# PCB-CMB-5-SHLD-3x5-1208.net
KiCad netlist of a schematic drawn in EAGLE
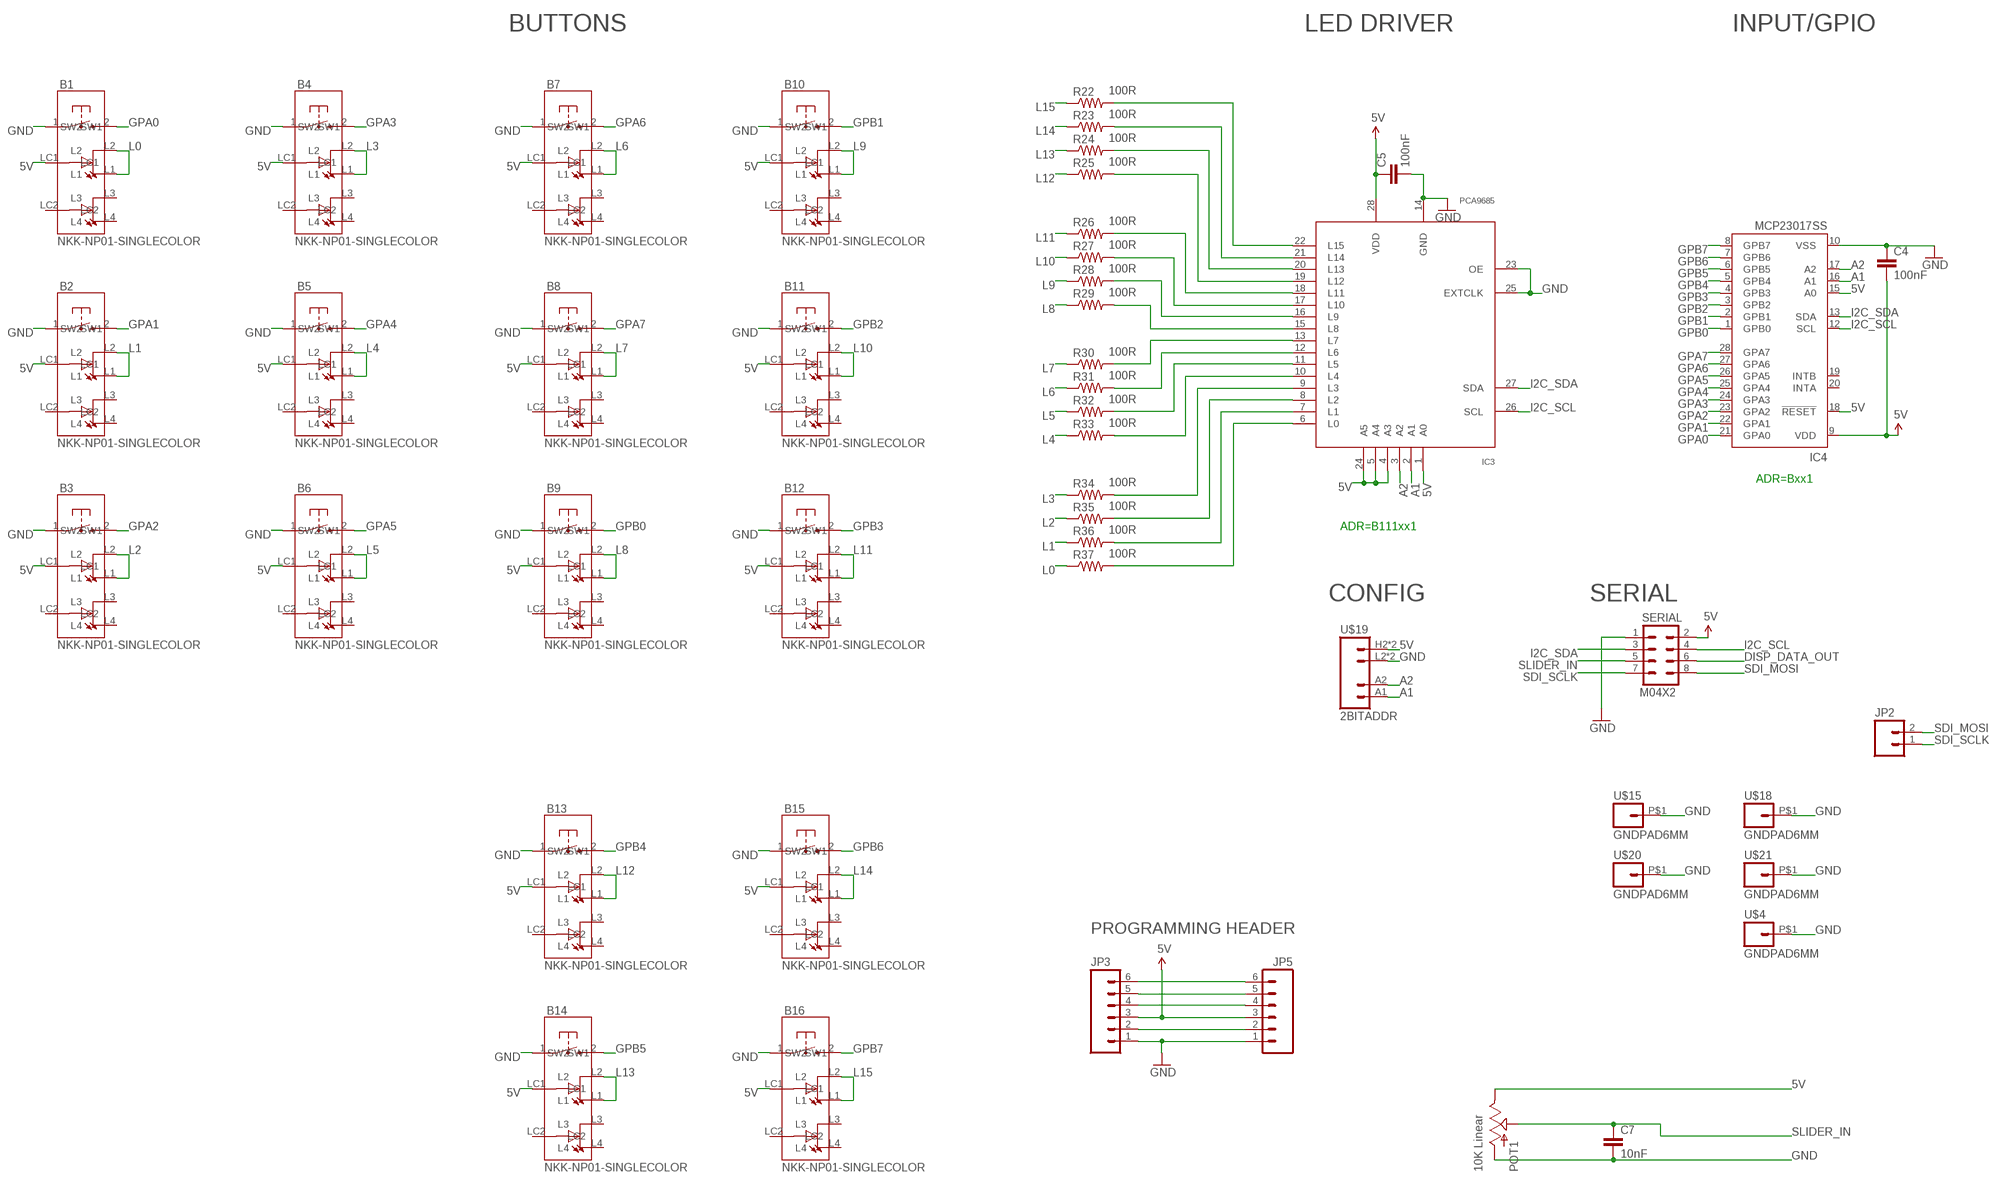
[diagram p0: schematic, sheet 1, part 1 of 2]
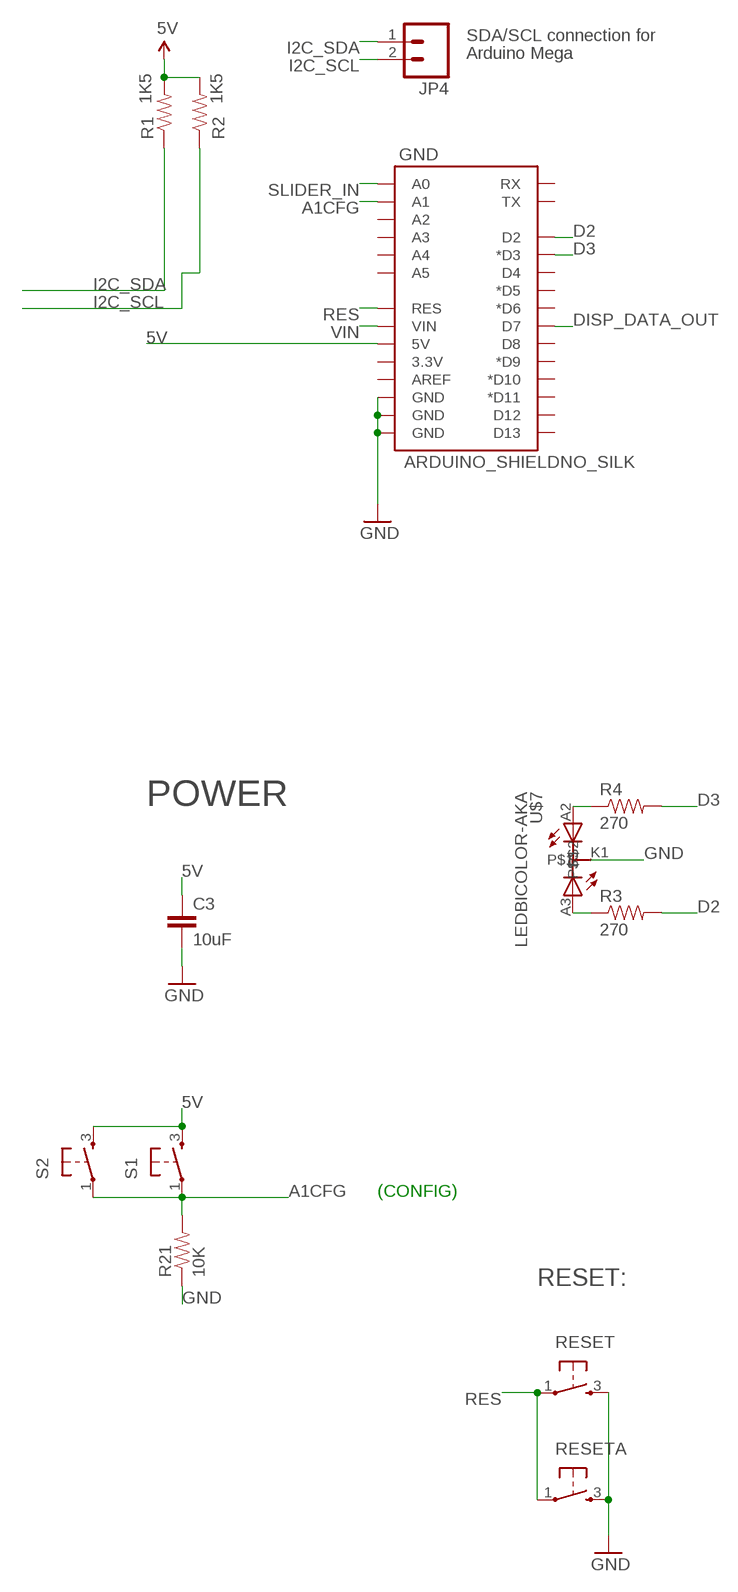
[diagram p1: schematic, sheet 1, part 2 of 2]

(export (version "E")
  (design (tool "Eeschema 10.0.6"))
  (components
    (comp (ref "B1")
      (value "NKK-NP01-SINGLECOLOR")
      (footprint "eagle-import:NKK-NP01")
      (libsource (lib "eagle-import") (part "NKK-NP01-SINGLECOLOR"))
    )
    (comp (ref "B2")
      (value "NKK-NP01-SINGLECOLOR")
      (footprint "eagle-import:NKK-NP01")
      (libsource (lib "eagle-import") (part "NKK-NP01-SINGLECOLOR"))
    )
    (comp (ref "B3")
      (value "NKK-NP01-SINGLECOLOR")
      (footprint "eagle-import:NKK-NP01")
      (libsource (lib "eagle-import") (part "NKK-NP01-SINGLECOLOR"))
    )
    (comp (ref "B4")
      (value "NKK-NP01-SINGLECOLOR")
      (footprint "eagle-import:NKK-NP01")
      (libsource (lib "eagle-import") (part "NKK-NP01-SINGLECOLOR"))
    )
    (comp (ref "B5")
      (value "NKK-NP01-SINGLECOLOR")
      (footprint "eagle-import:NKK-NP01")
      (libsource (lib "eagle-import") (part "NKK-NP01-SINGLECOLOR"))
    )
    (comp (ref "B6")
      (value "NKK-NP01-SINGLECOLOR")
      (footprint "eagle-import:NKK-NP01")
      (libsource (lib "eagle-import") (part "NKK-NP01-SINGLECOLOR"))
    )
    (comp (ref "B7")
      (value "NKK-NP01-SINGLECOLOR")
      (footprint "eagle-import:NKK-NP01")
      (libsource (lib "eagle-import") (part "NKK-NP01-SINGLECOLOR"))
    )
    (comp (ref "B8")
      (value "NKK-NP01-SINGLECOLOR")
      (footprint "eagle-import:NKK-NP01")
      (libsource (lib "eagle-import") (part "NKK-NP01-SINGLECOLOR"))
    )
    (comp (ref "B9")
      (value "NKK-NP01-SINGLECOLOR")
      (footprint "eagle-import:NKK-NP01")
      (libsource (lib "eagle-import") (part "NKK-NP01-SINGLECOLOR"))
    )
    (comp (ref "B10")
      (value "NKK-NP01-SINGLECOLOR")
      (footprint "eagle-import:NKK-NP01")
      (libsource (lib "eagle-import") (part "NKK-NP01-SINGLECOLOR"))
    )
    (comp (ref "B11")
      (value "NKK-NP01-SINGLECOLOR")
      (footprint "eagle-import:NKK-NP01")
      (libsource (lib "eagle-import") (part "NKK-NP01-SINGLECOLOR"))
    )
    (comp (ref "B12")
      (value "NKK-NP01-SINGLECOLOR")
      (footprint "eagle-import:NKK-NP01")
      (libsource (lib "eagle-import") (part "NKK-NP01-SINGLECOLOR"))
    )
    (comp (ref "B13")
      (value "NKK-NP01-SINGLECOLOR")
      (footprint "eagle-import:NKK-NP01")
      (libsource (lib "eagle-import") (part "NKK-NP01-SINGLECOLOR"))
    )
    (comp (ref "B14")
      (value "NKK-NP01-SINGLECOLOR")
      (footprint "eagle-import:NKK-NP01")
      (libsource (lib "eagle-import") (part "NKK-NP01-SINGLECOLOR"))
    )
    (comp (ref "B15")
      (value "NKK-NP01-SINGLECOLOR")
      (footprint "eagle-import:NKK-NP01")
      (libsource (lib "eagle-import") (part "NKK-NP01-SINGLECOLOR"))
    )
    (comp (ref "B16")
      (value "NKK-NP01-SINGLECOLOR")
      (footprint "eagle-import:NKK-NP01")
      (libsource (lib "eagle-import") (part "NKK-NP01-SINGLECOLOR"))
    )
    (comp (ref "C3")
      (value "10uF")
      (footprint "eagle-import:0805")
      (libsource (lib "eagle-import") (part "CAP0805"))
    )
    (comp (ref "C4")
      (value "100nF")
      (footprint "eagle-import:0603-CAP")
      (libsource (lib "eagle-import") (part "CAP0603-CAP"))
    )
    (comp (ref "C5")
      (value "100nF")
      (footprint "eagle-import:0603-CAP")
      (libsource (lib "eagle-import") (part "CAP0603-CAP"))
    )
    (comp (ref "C7")
      (value "10nF")
      (footprint "eagle-import:0603-CAP")
      (libsource (lib "eagle-import") (part "CAP0603-CAP"))
    )
    (comp (ref "GND")
      (value "ARDUINO_SHIELDNO_SILK")
      (footprint "eagle-import:DUEMILANOVE_VIAS")
      (libsource (lib "eagle-import") (part "ARDUINO_SHIELDNO_SILK"))
    )
    (comp (ref "IC3")
      (value "PCA9685")
      (footprint "eagle-import:TSSOP28")
      (libsource (lib "eagle-import") (part "PCA9685"))
    )
    (comp (ref "IC4")
      (value "MCP23017SS")
      (footprint "eagle-import:SSOP28")
      (fields
        (field (name "MF") "MICROCHIP")
        (field (name "MPN") "MCP23017-E/SS")
        (field (name "MPN_1") "MCP23017-E/SS")
        (field (name "OC_FARNELL") "1467674")
        (field (name "OC_NEWARK") "31K2960")
      )
      (libsource (lib "eagle-import") (part "MCP23017SS"))
    )
    (comp (ref "JP2")
      (value "M02PTH")
      (footprint "eagle-import:1X02")
      (libsource (lib "eagle-import") (part "M02PTH"))
    )
    (comp (ref "JP3")
      (value "M06POLAR")
      (footprint "eagle-import:MOLEX-1X6")
      (libsource (lib "eagle-import") (part "M06POLAR"))
    )
    (comp (ref "JP4")
      (value "M02PTH")
      (footprint "eagle-import:1X02")
      (libsource (lib "eagle-import") (part "M02PTH"))
    )
    (comp (ref "JP5")
      (value "M06POLAR")
      (footprint "eagle-import:MOLEX-1X6")
      (libsource (lib "eagle-import") (part "M06POLAR"))
    )
    (comp (ref "POT1")
      (value "10K Linear")
      (footprint "eagle-import:SLIDER20")
      (libsource (lib "eagle-import") (part "SLIDER20"))
    )
    (comp (ref "R1")
      (value "1K5")
      (footprint "eagle-import:0603-RES")
      (libsource (lib "eagle-import") (part "RESISTOR0603-RES"))
    )
    (comp (ref "R2")
      (value "1K5")
      (footprint "eagle-import:0603-RES")
      (libsource (lib "eagle-import") (part "RESISTOR0603-RES"))
    )
    (comp (ref "R3")
      (value "270")
      (footprint "eagle-import:0603-RES")
      (libsource (lib "eagle-import") (part "RESISTOR0603-RES"))
    )
    (comp (ref "R4")
      (value "270")
      (footprint "eagle-import:0603-RES")
      (libsource (lib "eagle-import") (part "RESISTOR0603-RES"))
    )
    (comp (ref "R21")
      (value "10K")
      (footprint "eagle-import:0603-RES")
      (libsource (lib "eagle-import") (part "RESISTOR0603-RES"))
    )
    (comp (ref "R22")
      (value "100R")
      (footprint "eagle-import:1206")
      (libsource (lib "eagle-import") (part "RESISTOR1206"))
    )
    (comp (ref "R23")
      (value "100R")
      (footprint "eagle-import:1206")
      (libsource (lib "eagle-import") (part "RESISTOR1206"))
    )
    (comp (ref "R24")
      (value "100R")
      (footprint "eagle-import:1206")
      (libsource (lib "eagle-import") (part "RESISTOR1206"))
    )
    (comp (ref "R25")
      (value "100R")
      (footprint "eagle-import:1206")
      (libsource (lib "eagle-import") (part "RESISTOR1206"))
    )
    (comp (ref "R26")
      (value "100R")
      (footprint "eagle-import:1206")
      (libsource (lib "eagle-import") (part "RESISTOR1206"))
    )
    (comp (ref "R27")
      (value "100R")
      (footprint "eagle-import:1206")
      (libsource (lib "eagle-import") (part "RESISTOR1206"))
    )
    (comp (ref "R28")
      (value "100R")
      (footprint "eagle-import:1206")
      (libsource (lib "eagle-import") (part "RESISTOR1206"))
    )
    (comp (ref "R29")
      (value "100R")
      (footprint "eagle-import:1206")
      (libsource (lib "eagle-import") (part "RESISTOR1206"))
    )
    (comp (ref "R30")
      (value "100R")
      (footprint "eagle-import:1206")
      (libsource (lib "eagle-import") (part "RESISTOR1206"))
    )
    (comp (ref "R31")
      (value "100R")
      (footprint "eagle-import:1206")
      (libsource (lib "eagle-import") (part "RESISTOR1206"))
    )
    (comp (ref "R32")
      (value "100R")
      (footprint "eagle-import:1206")
      (libsource (lib "eagle-import") (part "RESISTOR1206"))
    )
    (comp (ref "R33")
      (value "100R")
      (footprint "eagle-import:1206")
      (libsource (lib "eagle-import") (part "RESISTOR1206"))
    )
    (comp (ref "R34")
      (value "100R")
      (footprint "eagle-import:1206")
      (libsource (lib "eagle-import") (part "RESISTOR1206"))
    )
    (comp (ref "R35")
      (value "100R")
      (footprint "eagle-import:1206")
      (libsource (lib "eagle-import") (part "RESISTOR1206"))
    )
    (comp (ref "R36")
      (value "100R")
      (footprint "eagle-import:1206")
      (libsource (lib "eagle-import") (part "RESISTOR1206"))
    )
    (comp (ref "R37")
      (value "100R")
      (footprint "eagle-import:1206")
      (libsource (lib "eagle-import") (part "RESISTOR1206"))
    )
    (comp (ref "RESET")
      (value "TAC_SWITCH")
      (footprint "eagle-import:PUSHBUTTON")
      (libsource (lib "eagle-import") (part "TAC_SWITCH"))
    )
    (comp (ref "RESETA")
      (value "TAC_SWITCH")
      (footprint "eagle-import:PUSHBUTTON")
      (libsource (lib "eagle-import") (part "TAC_SWITCH"))
    )
    (comp (ref "S1")
      (value "TAC_SWITCH")
      (footprint "eagle-import:PUSHBUTTON")
      (libsource (lib "eagle-import") (part "TAC_SWITCH"))
    )
    (comp (ref "S2")
      (value "TAC_SWITCH")
      (footprint "eagle-import:PUSHBUTTON")
      (libsource (lib "eagle-import") (part "TAC_SWITCH"))
    )
    (comp (ref "SERIAL")
      (value "M04X2")
      (footprint "eagle-import:2X4")
      (libsource (lib "eagle-import") (part "M04X2"))
    )
    (comp (ref "U$4")
      (value "GNDPAD6MM")
      (footprint "eagle-import:3.2MMPAD6MM")
      (libsource (lib "eagle-import") (part "GNDPAD6MM"))
    )
    (comp (ref "U$7")
      (value "LEDBICOLOR-AKA")
      (footprint "eagle-import:LED5MM-BICOLOR")
      (libsource (lib "eagle-import") (part "LEDBICOLOR-AKA"))
    )
    (comp (ref "U$15")
      (value "GNDPAD6MM")
      (footprint "eagle-import:3.2MMPAD6MM")
      (libsource (lib "eagle-import") (part "GNDPAD6MM"))
    )
    (comp (ref "U$18")
      (value "GNDPAD6MM")
      (footprint "eagle-import:3.2MMPAD6MM")
      (libsource (lib "eagle-import") (part "GNDPAD6MM"))
    )
    (comp (ref "U$19")
      (value "2BITADDR")
      (footprint "eagle-import:2BITADDR")
      (libsource (lib "eagle-import") (part "2BITADDR"))
    )
    (comp (ref "U$20")
      (value "GNDPAD6MM")
      (footprint "eagle-import:3.2MMPAD6MM")
      (libsource (lib "eagle-import") (part "GNDPAD6MM"))
    )
    (comp (ref "U$21")
      (value "GNDPAD6MM")
      (footprint "eagle-import:3.2MMPAD6MM")
      (libsource (lib "eagle-import") (part "GNDPAD6MM"))
    )
  )
  (nets
    (net (code "1") (name "5V") (class "Default")
      (node (ref "B1") (pin "LC1") (pinfunction "LC1_LC1") (pintype "bidirectional"))
      (node (ref "B10") (pin "LC1") (pinfunction "LC1_LC1") (pintype "bidirectional"))
      (node (ref "B11") (pin "LC1") (pinfunction "LC1_LC1") (pintype "bidirectional"))
      (node (ref "B12") (pin "LC1") (pinfunction "LC1_LC1") (pintype "bidirectional"))
      (node (ref "B13") (pin "LC1") (pinfunction "LC1_LC1") (pintype "bidirectional"))
      (node (ref "B14") (pin "LC1") (pinfunction "LC1_LC1") (pintype "bidirectional"))
      (node (ref "B15") (pin "LC1") (pinfunction "LC1_LC1") (pintype "bidirectional"))
      (node (ref "B16") (pin "LC1") (pinfunction "LC1_LC1") (pintype "bidirectional"))
      (node (ref "B2") (pin "LC1") (pinfunction "LC1_LC1") (pintype "bidirectional"))
      (node (ref "B3") (pin "LC1") (pinfunction "LC1_LC1") (pintype "bidirectional"))
      (node (ref "B4") (pin "LC1") (pinfunction "LC1_LC1") (pintype "bidirectional"))
      (node (ref "B5") (pin "LC1") (pinfunction "LC1_LC1") (pintype "bidirectional"))
      (node (ref "B6") (pin "LC1") (pinfunction "LC1_LC1") (pintype "bidirectional"))
      (node (ref "B7") (pin "LC1") (pinfunction "LC1_LC1") (pintype "bidirectional"))
      (node (ref "B8") (pin "LC1") (pinfunction "LC1_LC1") (pintype "bidirectional"))
      (node (ref "B9") (pin "LC1") (pinfunction "LC1_LC1") (pintype "bidirectional"))
      (node (ref "C3") (pin "1") (pinfunction "1_1") (pintype "passive"))
      (node (ref "C4") (pin "2") (pinfunction "2_2") (pintype "passive"))
      (node (ref "C5") (pin "1") (pinfunction "1_1") (pintype "passive"))
      (node (ref "GND") (pin "5V") (pinfunction "5V_5V") (pintype "bidirectional"))
      (node (ref "IC3") (pin "1") (pinfunction "A0_1") (pintype "input"))
      (node (ref "IC3") (pin "24") (pinfunction "A5_24") (pintype "input"))
      (node (ref "IC3") (pin "28") (pinfunction "VDD_28") (pintype "power_in"))
      (node (ref "IC3") (pin "4") (pinfunction "A3_4") (pintype "input"))
      (node (ref "IC3") (pin "5") (pinfunction "A4_5") (pintype "input"))
      (node (ref "IC4") (pin "15") (pinfunction "A0_15") (pintype "input"))
      (node (ref "IC4") (pin "18") (pinfunction "~{RESET}_18") (pintype "input"))
      (node (ref "IC4") (pin "9") (pinfunction "VDD_9") (pintype "power_in"))
      (node (ref "JP3") (pin "3") (pinfunction "3_3") (pintype "passive"))
      (node (ref "JP5") (pin "3") (pinfunction "3_3") (pintype "passive"))
      (node (ref "POT1") (pin "1") (pinfunction "E_1") (pintype "passive"))
      (node (ref "R1") (pin "2") (pinfunction "2_2") (pintype "passive"))
      (node (ref "R2") (pin "2") (pinfunction "2_2") (pintype "passive"))
      (node (ref "S1") (pin "3") (pinfunction "3_3") (pintype "passive"))
      (node (ref "S2") (pin "3") (pinfunction "3_3") (pintype "passive"))
      (node (ref "SERIAL") (pin "2") (pinfunction "2_2") (pintype "passive"))
      (node (ref "U$19") (pin "H2") (pinfunction "VCC_H2") (pintype "passive"))
      (node (ref "U$19") (pin "H3") (pinfunction "VCC_H3") (pintype "passive"))
    )
    (net (code "2") (name "A1") (class "Default")
      (node (ref "IC3") (pin "2") (pinfunction "A1_2") (pintype "input"))
      (node (ref "IC4") (pin "16") (pinfunction "A1_16") (pintype "input"))
      (node (ref "U$19") (pin "A1") (pinfunction "A1_A1") (pintype "passive"))
    )
    (net (code "3") (name "A1CFG") (class "Default")
      (node (ref "GND") (pin "A1") (pinfunction "A1_A1") (pintype "bidirectional"))
      (node (ref "R21") (pin "2") (pinfunction "2_2") (pintype "passive"))
      (node (ref "S1") (pin "1") (pinfunction "1_1") (pintype "passive"))
      (node (ref "S2") (pin "1") (pinfunction "1_1") (pintype "passive"))
    )
    (net (code "4") (name "A2") (class "Default")
      (node (ref "IC3") (pin "3") (pinfunction "A2_3") (pintype "input"))
      (node (ref "IC4") (pin "17") (pinfunction "A2_17") (pintype "input"))
      (node (ref "U$19") (pin "A2") (pinfunction "A2_A2") (pintype "passive"))
    )
    (net (code "5") (name "D2") (class "Default")
      (node (ref "GND") (pin "D2") (pinfunction "D2_D2") (pintype "bidirectional"))
      (node (ref "R3") (pin "2") (pinfunction "2_2") (pintype "passive"))
    )
    (net (code "6") (name "D3") (class "Default")
      (node (ref "GND") (pin "D3") (pinfunction "*D3_D3") (pintype "bidirectional"))
      (node (ref "R4") (pin "2") (pinfunction "2_2") (pintype "passive"))
    )
    (net (code "7") (name "DISP_DATA_OUT") (class "Default")
      (node (ref "GND") (pin "D7") (pinfunction "D7_D7") (pintype "bidirectional"))
      (node (ref "SERIAL") (pin "6") (pinfunction "6_6") (pintype "passive"))
    )
    (net (code "8") (name "GND") (class "Default")
      (node (ref "B1") (pin "1") (pinfunction "SW1_1") (pintype "bidirectional"))
      (node (ref "B10") (pin "1") (pinfunction "SW1_1") (pintype "bidirectional"))
      (node (ref "B11") (pin "1") (pinfunction "SW1_1") (pintype "bidirectional"))
      (node (ref "B12") (pin "1") (pinfunction "SW1_1") (pintype "bidirectional"))
      (node (ref "B13") (pin "1") (pinfunction "SW1_1") (pintype "bidirectional"))
      (node (ref "B14") (pin "1") (pinfunction "SW1_1") (pintype "bidirectional"))
      (node (ref "B15") (pin "1") (pinfunction "SW1_1") (pintype "bidirectional"))
      (node (ref "B16") (pin "1") (pinfunction "SW1_1") (pintype "bidirectional"))
      (node (ref "B2") (pin "1") (pinfunction "SW1_1") (pintype "bidirectional"))
      (node (ref "B3") (pin "1") (pinfunction "SW1_1") (pintype "bidirectional"))
      (node (ref "B4") (pin "1") (pinfunction "SW1_1") (pintype "bidirectional"))
      (node (ref "B5") (pin "1") (pinfunction "SW1_1") (pintype "bidirectional"))
      (node (ref "B6") (pin "1") (pinfunction "SW1_1") (pintype "bidirectional"))
      (node (ref "B7") (pin "1") (pinfunction "SW1_1") (pintype "bidirectional"))
      (node (ref "B8") (pin "1") (pinfunction "SW1_1") (pintype "bidirectional"))
      (node (ref "B9") (pin "1") (pinfunction "SW1_1") (pintype "bidirectional"))
      (node (ref "C3") (pin "2") (pinfunction "2_2") (pintype "passive"))
      (node (ref "C4") (pin "1") (pinfunction "1_1") (pintype "passive"))
      (node (ref "C5") (pin "2") (pinfunction "2_2") (pintype "passive"))
      (node (ref "C7") (pin "2") (pinfunction "2_2") (pintype "passive"))
      (node (ref "GND") (pin "GND@0") (pinfunction "GND_GND@0") (pintype "bidirectional"))
      (node (ref "GND") (pin "GND@1") (pinfunction "GND_GND@1") (pintype "bidirectional"))
      (node (ref "GND") (pin "GND@2") (pinfunction "GND_GND@2") (pintype "bidirectional"))
      (node (ref "IC3") (pin "14") (pinfunction "GND_14") (pintype "power_in"))
      (node (ref "IC3") (pin "23") (pinfunction "OE_23") (pintype "input"))
      (node (ref "IC3") (pin "25") (pinfunction "EXTCLK_25") (pintype "input"))
      (node (ref "IC4") (pin "10") (pinfunction "VSS_10") (pintype "power_in"))
      (node (ref "JP3") (pin "1") (pinfunction "1_1") (pintype "passive"))
      (node (ref "JP5") (pin "1") (pinfunction "1_1") (pintype "passive"))
      (node (ref "POT1") (pin "3") (pinfunction "A_3") (pintype "passive"))
      (node (ref "R21") (pin "1") (pinfunction "1_1") (pintype "passive"))
      (node (ref "RESET") (pin "3") (pinfunction "3_3") (pintype "passive"))
      (node (ref "RESETA") (pin "3") (pinfunction "3_3") (pintype "passive"))
      (node (ref "SERIAL") (pin "1") (pinfunction "1_1") (pintype "passive"))
      (node (ref "U$15") (pin "P$1") (pinfunction "1_P$1") (pintype "passive"))
      (node (ref "U$18") (pin "P$1") (pinfunction "1_P$1") (pintype "passive"))
      (node (ref "U$19") (pin "L2") (pinfunction "GND_L2") (pintype "passive"))
      (node (ref "U$19") (pin "L3") (pinfunction "GND_L3") (pintype "passive"))
      (node (ref "U$20") (pin "P$1") (pinfunction "1_P$1") (pintype "passive"))
      (node (ref "U$21") (pin "P$1") (pinfunction "1_P$1") (pintype "passive"))
      (node (ref "U$4") (pin "P$1") (pinfunction "1_P$1") (pintype "passive"))
      (node (ref "U$7") (pin "K1") (pinfunction "P$1_K1") (pintype "bidirectional"))
    )
    (net (code "9") (name "GPA0") (class "Default")
      (node (ref "B1") (pin "2") (pinfunction "SW2_2") (pintype "bidirectional"))
      (node (ref "IC4") (pin "21") (pinfunction "GPA0_21") (pintype "bidirectional"))
    )
    (net (code "10") (name "GPA1") (class "Default")
      (node (ref "B2") (pin "2") (pinfunction "SW2_2") (pintype "bidirectional"))
      (node (ref "IC4") (pin "22") (pinfunction "GPA1_22") (pintype "bidirectional"))
    )
    (net (code "11") (name "GPA2") (class "Default")
      (node (ref "B3") (pin "2") (pinfunction "SW2_2") (pintype "bidirectional"))
      (node (ref "IC4") (pin "23") (pinfunction "GPA2_23") (pintype "bidirectional"))
    )
    (net (code "12") (name "GPA3") (class "Default")
      (node (ref "B4") (pin "2") (pinfunction "SW2_2") (pintype "bidirectional"))
      (node (ref "IC4") (pin "24") (pinfunction "GPA3_24") (pintype "bidirectional"))
    )
    (net (code "13") (name "GPA4") (class "Default")
      (node (ref "B5") (pin "2") (pinfunction "SW2_2") (pintype "bidirectional"))
      (node (ref "IC4") (pin "25") (pinfunction "GPA4_25") (pintype "bidirectional"))
    )
    (net (code "14") (name "GPA5") (class "Default")
      (node (ref "B6") (pin "2") (pinfunction "SW2_2") (pintype "bidirectional"))
      (node (ref "IC4") (pin "26") (pinfunction "GPA5_26") (pintype "bidirectional"))
    )
    (net (code "15") (name "GPA6") (class "Default")
      (node (ref "B7") (pin "2") (pinfunction "SW2_2") (pintype "bidirectional"))
      (node (ref "IC4") (pin "27") (pinfunction "GPA6_27") (pintype "bidirectional"))
    )
    (net (code "16") (name "GPA7") (class "Default")
      (node (ref "B8") (pin "2") (pinfunction "SW2_2") (pintype "bidirectional"))
      (node (ref "IC4") (pin "28") (pinfunction "GPA7_28") (pintype "bidirectional"))
    )
    (net (code "17") (name "GPB0") (class "Default")
      (node (ref "B9") (pin "2") (pinfunction "SW2_2") (pintype "bidirectional"))
      (node (ref "IC4") (pin "1") (pinfunction "GPB0_1") (pintype "bidirectional"))
    )
    (net (code "18") (name "GPB1") (class "Default")
      (node (ref "B10") (pin "2") (pinfunction "SW2_2") (pintype "bidirectional"))
      (node (ref "IC4") (pin "2") (pinfunction "GPB1_2") (pintype "bidirectional"))
    )
    (net (code "19") (name "GPB2") (class "Default")
      (node (ref "B11") (pin "2") (pinfunction "SW2_2") (pintype "bidirectional"))
      (node (ref "IC4") (pin "3") (pinfunction "GPB2_3") (pintype "bidirectional"))
    )
    (net (code "20") (name "GPB3") (class "Default")
      (node (ref "B12") (pin "2") (pinfunction "SW2_2") (pintype "bidirectional"))
      (node (ref "IC4") (pin "4") (pinfunction "GPB3_4") (pintype "bidirectional"))
    )
    (net (code "21") (name "GPB4") (class "Default")
      (node (ref "B13") (pin "2") (pinfunction "SW2_2") (pintype "bidirectional"))
      (node (ref "IC4") (pin "5") (pinfunction "GPB4_5") (pintype "bidirectional"))
    )
    (net (code "22") (name "GPB5") (class "Default")
      (node (ref "B14") (pin "2") (pinfunction "SW2_2") (pintype "bidirectional"))
      (node (ref "IC4") (pin "6") (pinfunction "GPB5_6") (pintype "bidirectional"))
    )
    (net (code "23") (name "GPB6") (class "Default")
      (node (ref "B15") (pin "2") (pinfunction "SW2_2") (pintype "bidirectional"))
      (node (ref "IC4") (pin "7") (pinfunction "GPB6_7") (pintype "bidirectional"))
    )
    (net (code "24") (name "GPB7") (class "Default")
      (node (ref "B16") (pin "2") (pinfunction "SW2_2") (pintype "bidirectional"))
      (node (ref "IC4") (pin "8") (pinfunction "GPB7_8") (pintype "bidirectional"))
    )
    (net (code "25") (name "I2C_SCL") (class "Default")
      (node (ref "IC3") (pin "26") (pinfunction "SCL_26") (pintype "input"))
      (node (ref "IC4") (pin "12") (pinfunction "SCL_12") (pintype "input"))
      (node (ref "JP4") (pin "2") (pinfunction "2_2") (pintype "passive"))
      (node (ref "R2") (pin "1") (pinfunction "1_1") (pintype "passive"))
      (node (ref "SERIAL") (pin "4") (pinfunction "4_4") (pintype "passive"))
    )
    (net (code "26") (name "I2C_SDA") (class "Default")
      (node (ref "IC3") (pin "27") (pinfunction "SDA_27") (pintype "input"))
      (node (ref "IC4") (pin "13") (pinfunction "SDA_13") (pintype "bidirectional"))
      (node (ref "JP4") (pin "1") (pinfunction "1_1") (pintype "passive"))
      (node (ref "R1") (pin "1") (pinfunction "1_1") (pintype "passive"))
      (node (ref "SERIAL") (pin "3") (pinfunction "3_3") (pintype "passive"))
    )
    (net (code "27") (name "L0") (class "Default")
      (node (ref "B1") (pin "L1") (pinfunction "L1_L1") (pintype "bidirectional"))
      (node (ref "B1") (pin "L2") (pinfunction "L2_L2") (pintype "bidirectional"))
      (node (ref "R37") (pin "1") (pinfunction "1_1") (pintype "passive"))
    )
    (net (code "28") (name "L1") (class "Default")
      (node (ref "B2") (pin "L1") (pinfunction "L1_L1") (pintype "bidirectional"))
      (node (ref "B2") (pin "L2") (pinfunction "L2_L2") (pintype "bidirectional"))
      (node (ref "R36") (pin "1") (pinfunction "1_1") (pintype "passive"))
    )
    (net (code "29") (name "L2") (class "Default")
      (node (ref "B3") (pin "L1") (pinfunction "L1_L1") (pintype "bidirectional"))
      (node (ref "B3") (pin "L2") (pinfunction "L2_L2") (pintype "bidirectional"))
      (node (ref "R35") (pin "1") (pinfunction "1_1") (pintype "passive"))
    )
    (net (code "30") (name "L3") (class "Default")
      (node (ref "B4") (pin "L1") (pinfunction "L1_L1") (pintype "bidirectional"))
      (node (ref "B4") (pin "L2") (pinfunction "L2_L2") (pintype "bidirectional"))
      (node (ref "R34") (pin "1") (pinfunction "1_1") (pintype "passive"))
    )
    (net (code "31") (name "L4") (class "Default")
      (node (ref "B5") (pin "L1") (pinfunction "L1_L1") (pintype "bidirectional"))
      (node (ref "B5") (pin "L2") (pinfunction "L2_L2") (pintype "bidirectional"))
      (node (ref "R33") (pin "1") (pinfunction "1_1") (pintype "passive"))
    )
    (net (code "32") (name "L5") (class "Default")
      (node (ref "B6") (pin "L1") (pinfunction "L1_L1") (pintype "bidirectional"))
      (node (ref "B6") (pin "L2") (pinfunction "L2_L2") (pintype "bidirectional"))
      (node (ref "R32") (pin "1") (pinfunction "1_1") (pintype "passive"))
    )
    (net (code "33") (name "L6") (class "Default")
      (node (ref "B7") (pin "L1") (pinfunction "L1_L1") (pintype "bidirectional"))
      (node (ref "B7") (pin "L2") (pinfunction "L2_L2") (pintype "bidirectional"))
      (node (ref "R31") (pin "1") (pinfunction "1_1") (pintype "passive"))
    )
    (net (code "34") (name "L7") (class "Default")
      (node (ref "B8") (pin "L1") (pinfunction "L1_L1") (pintype "bidirectional"))
      (node (ref "B8") (pin "L2") (pinfunction "L2_L2") (pintype "bidirectional"))
      (node (ref "R30") (pin "1") (pinfunction "1_1") (pintype "passive"))
    )
    (net (code "35") (name "L8") (class "Default")
      (node (ref "B9") (pin "L1") (pinfunction "L1_L1") (pintype "bidirectional"))
      (node (ref "B9") (pin "L2") (pinfunction "L2_L2") (pintype "bidirectional"))
      (node (ref "R29") (pin "1") (pinfunction "1_1") (pintype "passive"))
    )
    (net (code "36") (name "L9") (class "Default")
      (node (ref "B10") (pin "L1") (pinfunction "L1_L1") (pintype "bidirectional"))
      (node (ref "B10") (pin "L2") (pinfunction "L2_L2") (pintype "bidirectional"))
      (node (ref "R28") (pin "1") (pinfunction "1_1") (pintype "passive"))
    )
    (net (code "37") (name "L10") (class "Default")
      (node (ref "B11") (pin "L1") (pinfunction "L1_L1") (pintype "bidirectional"))
      (node (ref "B11") (pin "L2") (pinfunction "L2_L2") (pintype "bidirectional"))
      (node (ref "R27") (pin "1") (pinfunction "1_1") (pintype "passive"))
    )
    (net (code "38") (name "L11") (class "Default")
      (node (ref "B12") (pin "L1") (pinfunction "L1_L1") (pintype "bidirectional"))
      (node (ref "B12") (pin "L2") (pinfunction "L2_L2") (pintype "bidirectional"))
      (node (ref "R26") (pin "1") (pinfunction "1_1") (pintype "passive"))
    )
    (net (code "39") (name "L12") (class "Default")
      (node (ref "B13") (pin "L1") (pinfunction "L1_L1") (pintype "bidirectional"))
      (node (ref "B13") (pin "L2") (pinfunction "L2_L2") (pintype "bidirectional"))
      (node (ref "R25") (pin "1") (pinfunction "1_1") (pintype "passive"))
    )
    (net (code "40") (name "L13") (class "Default")
      (node (ref "B14") (pin "L1") (pinfunction "L1_L1") (pintype "bidirectional"))
      (node (ref "B14") (pin "L2") (pinfunction "L2_L2") (pintype "bidirectional"))
      (node (ref "R24") (pin "1") (pinfunction "1_1") (pintype "passive"))
    )
    (net (code "41") (name "L14") (class "Default")
      (node (ref "B15") (pin "L1") (pinfunction "L1_L1") (pintype "bidirectional"))
      (node (ref "B15") (pin "L2") (pinfunction "L2_L2") (pintype "bidirectional"))
      (node (ref "R23") (pin "1") (pinfunction "1_1") (pintype "passive"))
    )
    (net (code "42") (name "L15") (class "Default")
      (node (ref "B16") (pin "L1") (pinfunction "L1_L1") (pintype "bidirectional"))
      (node (ref "B16") (pin "L2") (pinfunction "L2_L2") (pintype "bidirectional"))
      (node (ref "R22") (pin "1") (pinfunction "1_1") (pintype "passive"))
    )
    (net (code "43") (name "Net-(IC3-L0)") (class "Default")
      (node (ref "IC3") (pin "6") (pinfunction "L0_6") (pintype "output"))
      (node (ref "R37") (pin "2") (pinfunction "2_2") (pintype "passive"))
    )
    (net (code "44") (name "Net-(IC3-L1)") (class "Default")
      (node (ref "IC3") (pin "7") (pinfunction "L1_7") (pintype "output"))
      (node (ref "R36") (pin "2") (pinfunction "2_2") (pintype "passive"))
    )
    (net (code "45") (name "Net-(IC3-L2)") (class "Default")
      (node (ref "IC3") (pin "8") (pinfunction "L2_8") (pintype "output"))
      (node (ref "R35") (pin "2") (pinfunction "2_2") (pintype "passive"))
    )
    (net (code "46") (name "Net-(IC3-L3)") (class "Default")
      (node (ref "IC3") (pin "9") (pinfunction "L3_9") (pintype "output"))
      (node (ref "R34") (pin "2") (pinfunction "2_2") (pintype "passive"))
    )
    (net (code "47") (name "Net-(IC3-L4)") (class "Default")
      (node (ref "IC3") (pin "10") (pinfunction "L4_10") (pintype "output"))
      (node (ref "R33") (pin "2") (pinfunction "2_2") (pintype "passive"))
    )
    (net (code "48") (name "Net-(IC3-L5)") (class "Default")
      (node (ref "IC3") (pin "11") (pinfunction "L5_11") (pintype "output"))
      (node (ref "R32") (pin "2") (pinfunction "2_2") (pintype "passive"))
    )
    (net (code "49") (name "Net-(IC3-L6)") (class "Default")
      (node (ref "IC3") (pin "12") (pinfunction "L6_12") (pintype "output"))
      (node (ref "R31") (pin "2") (pinfunction "2_2") (pintype "passive"))
    )
    (net (code "50") (name "Net-(IC3-L7)") (class "Default")
      (node (ref "IC3") (pin "13") (pinfunction "L7_13") (pintype "output"))
      (node (ref "R30") (pin "2") (pinfunction "2_2") (pintype "passive"))
    )
    (net (code "51") (name "Net-(IC3-L8)") (class "Default")
      (node (ref "IC3") (pin "15") (pinfunction "L8_15") (pintype "output"))
      (node (ref "R29") (pin "2") (pinfunction "2_2") (pintype "passive"))
    )
    (net (code "52") (name "Net-(IC3-L9)") (class "Default")
      (node (ref "IC3") (pin "16") (pinfunction "L9_16") (pintype "output"))
      (node (ref "R28") (pin "2") (pinfunction "2_2") (pintype "passive"))
    )
    (net (code "53") (name "Net-(IC3-L10)") (class "Default")
      (node (ref "IC3") (pin "17") (pinfunction "L10_17") (pintype "output"))
      (node (ref "R27") (pin "2") (pinfunction "2_2") (pintype "passive"))
    )
    (net (code "54") (name "Net-(IC3-L11)") (class "Default")
      (node (ref "IC3") (pin "18") (pinfunction "L11_18") (pintype "output"))
      (node (ref "R26") (pin "2") (pinfunction "2_2") (pintype "passive"))
    )
    (net (code "55") (name "Net-(IC3-L12)") (class "Default")
      (node (ref "IC3") (pin "19") (pinfunction "L12_19") (pintype "output"))
      (node (ref "R25") (pin "2") (pinfunction "2_2") (pintype "passive"))
    )
    (net (code "56") (name "Net-(IC3-L13)") (class "Default")
      (node (ref "IC3") (pin "20") (pinfunction "L13_20") (pintype "output"))
      (node (ref "R24") (pin "2") (pinfunction "2_2") (pintype "passive"))
    )
    (net (code "57") (name "Net-(IC3-L14)") (class "Default")
      (node (ref "IC3") (pin "21") (pinfunction "L14_21") (pintype "output"))
      (node (ref "R23") (pin "2") (pinfunction "2_2") (pintype "passive"))
    )
    (net (code "58") (name "Net-(IC3-L15)") (class "Default")
      (node (ref "IC3") (pin "22") (pinfunction "L15_22") (pintype "output"))
      (node (ref "R22") (pin "2") (pinfunction "2_2") (pintype "passive"))
    )
    (net (code "59") (name "Net-(JP3-Pad2)") (class "Default")
      (node (ref "JP3") (pin "2") (pinfunction "2_2") (pintype "passive"))
      (node (ref "JP5") (pin "2") (pinfunction "2_2") (pintype "passive"))
    )
    (net (code "60") (name "Net-(JP3-Pad4)") (class "Default")
      (node (ref "JP3") (pin "4") (pinfunction "4_4") (pintype "passive"))
      (node (ref "JP5") (pin "4") (pinfunction "4_4") (pintype "passive"))
    )
    (net (code "61") (name "Net-(JP3-Pad5)") (class "Default")
      (node (ref "JP3") (pin "5") (pinfunction "5_5") (pintype "passive"))
      (node (ref "JP5") (pin "5") (pinfunction "5_5") (pintype "passive"))
    )
    (net (code "62") (name "Net-(JP3-Pad6)") (class "Default")
      (node (ref "JP3") (pin "6") (pinfunction "6_6") (pintype "passive"))
      (node (ref "JP5") (pin "6") (pinfunction "6_6") (pintype "passive"))
    )
    (net (code "63") (name "Net-(U$7-P$2)") (class "Default")
      (node (ref "R4") (pin "1") (pinfunction "1_1") (pintype "passive"))
      (node (ref "U$7") (pin "A2") (pinfunction "P$2_A2") (pintype "bidirectional"))
    )
    (net (code "64") (name "Net-(U$7-P$3)") (class "Default")
      (node (ref "R3") (pin "1") (pinfunction "1_1") (pintype "passive"))
      (node (ref "U$7") (pin "A3") (pinfunction "P$3_A3") (pintype "bidirectional"))
    )
    (net (code "65") (name "RES") (class "Default")
      (node (ref "GND") (pin "RES") (pinfunction "RES_RES") (pintype "bidirectional"))
      (node (ref "RESET") (pin "1") (pinfunction "1_1") (pintype "passive"))
      (node (ref "RESETA") (pin "1") (pinfunction "1_1") (pintype "passive"))
    )
    (net (code "66") (name "SDI_MOSI") (class "Default")
      (node (ref "JP2") (pin "2") (pinfunction "2_2") (pintype "passive"))
      (node (ref "SERIAL") (pin "8") (pinfunction "8_8") (pintype "passive"))
    )
    (net (code "67") (name "SDI_SCLK") (class "Default")
      (node (ref "JP2") (pin "1") (pinfunction "1_1") (pintype "passive"))
      (node (ref "SERIAL") (pin "7") (pinfunction "7_7") (pintype "passive"))
    )
    (net (code "68") (name "SLIDER_IN") (class "Default")
      (node (ref "C7") (pin "1") (pinfunction "1_1") (pintype "passive"))
      (node (ref "GND") (pin "A0") (pinfunction "A0_A0") (pintype "bidirectional"))
      (node (ref "POT1") (pin "2A") (pinfunction "S_2A") (pintype "passive"))
      (node (ref "SERIAL") (pin "5") (pinfunction "5_5") (pintype "passive"))
    )
    (net (code "69") (name "VIN") (class "Default")
      (node (ref "GND") (pin "VIN") (pinfunction "VIN_VIN") (pintype "bidirectional"))
    )
    (net (code "70") (name "unconnected-(B1-PadL3)") (class "Default")
      (node (ref "B1") (pin "L3") (pinfunction "L3_L3") (pintype "bidirectional"))
    )
    (net (code "71") (name "unconnected-(B1-PadL4)") (class "Default")
      (node (ref "B1") (pin "L4") (pinfunction "L4_L4") (pintype "bidirectional"))
    )
    (net (code "72") (name "unconnected-(B1-PadLC2)") (class "Default")
      (node (ref "B1") (pin "LC2") (pinfunction "LC2_LC2") (pintype "bidirectional"))
    )
    (net (code "73") (name "unconnected-(B2-PadL3)") (class "Default")
      (node (ref "B2") (pin "L3") (pinfunction "L3_L3") (pintype "bidirectional"))
    )
    (net (code "74") (name "unconnected-(B2-PadL4)") (class "Default")
      (node (ref "B2") (pin "L4") (pinfunction "L4_L4") (pintype "bidirectional"))
    )
    (net (code "75") (name "unconnected-(B2-PadLC2)") (class "Default")
      (node (ref "B2") (pin "LC2") (pinfunction "LC2_LC2") (pintype "bidirectional"))
    )
    (net (code "76") (name "unconnected-(B3-PadL3)") (class "Default")
      (node (ref "B3") (pin "L3") (pinfunction "L3_L3") (pintype "bidirectional"))
    )
    (net (code "77") (name "unconnected-(B3-PadL4)") (class "Default")
      (node (ref "B3") (pin "L4") (pinfunction "L4_L4") (pintype "bidirectional"))
    )
    (net (code "78") (name "unconnected-(B3-PadLC2)") (class "Default")
      (node (ref "B3") (pin "LC2") (pinfunction "LC2_LC2") (pintype "bidirectional"))
    )
    (net (code "79") (name "unconnected-(B4-PadL3)") (class "Default")
      (node (ref "B4") (pin "L3") (pinfunction "L3_L3") (pintype "bidirectional"))
    )
    (net (code "80") (name "unconnected-(B4-PadL4)") (class "Default")
      (node (ref "B4") (pin "L4") (pinfunction "L4_L4") (pintype "bidirectional"))
    )
    (net (code "81") (name "unconnected-(B4-PadLC2)") (class "Default")
      (node (ref "B4") (pin "LC2") (pinfunction "LC2_LC2") (pintype "bidirectional"))
    )
    (net (code "82") (name "unconnected-(B5-PadL3)") (class "Default")
      (node (ref "B5") (pin "L3") (pinfunction "L3_L3") (pintype "bidirectional"))
    )
    (net (code "83") (name "unconnected-(B5-PadL4)") (class "Default")
      (node (ref "B5") (pin "L4") (pinfunction "L4_L4") (pintype "bidirectional"))
    )
    (net (code "84") (name "unconnected-(B5-PadLC2)") (class "Default")
      (node (ref "B5") (pin "LC2") (pinfunction "LC2_LC2") (pintype "bidirectional"))
    )
    (net (code "85") (name "unconnected-(B6-PadL3)") (class "Default")
      (node (ref "B6") (pin "L3") (pinfunction "L3_L3") (pintype "bidirectional"))
    )
    (net (code "86") (name "unconnected-(B6-PadL4)") (class "Default")
      (node (ref "B6") (pin "L4") (pinfunction "L4_L4") (pintype "bidirectional"))
    )
    (net (code "87") (name "unconnected-(B6-PadLC2)") (class "Default")
      (node (ref "B6") (pin "LC2") (pinfunction "LC2_LC2") (pintype "bidirectional"))
    )
    (net (code "88") (name "unconnected-(B7-PadL3)") (class "Default")
      (node (ref "B7") (pin "L3") (pinfunction "L3_L3") (pintype "bidirectional"))
    )
    (net (code "89") (name "unconnected-(B7-PadL4)") (class "Default")
      (node (ref "B7") (pin "L4") (pinfunction "L4_L4") (pintype "bidirectional"))
    )
    (net (code "90") (name "unconnected-(B7-PadLC2)") (class "Default")
      (node (ref "B7") (pin "LC2") (pinfunction "LC2_LC2") (pintype "bidirectional"))
    )
    (net (code "91") (name "unconnected-(B8-PadL3)") (class "Default")
      (node (ref "B8") (pin "L3") (pinfunction "L3_L3") (pintype "bidirectional"))
    )
    (net (code "92") (name "unconnected-(B8-PadL4)") (class "Default")
      (node (ref "B8") (pin "L4") (pinfunction "L4_L4") (pintype "bidirectional"))
    )
    (net (code "93") (name "unconnected-(B8-PadLC2)") (class "Default")
      (node (ref "B8") (pin "LC2") (pinfunction "LC2_LC2") (pintype "bidirectional"))
    )
    (net (code "94") (name "unconnected-(B9-PadL3)") (class "Default")
      (node (ref "B9") (pin "L3") (pinfunction "L3_L3") (pintype "bidirectional"))
    )
    (net (code "95") (name "unconnected-(B9-PadL4)") (class "Default")
      (node (ref "B9") (pin "L4") (pinfunction "L4_L4") (pintype "bidirectional"))
    )
    (net (code "96") (name "unconnected-(B9-PadLC2)") (class "Default")
      (node (ref "B9") (pin "LC2") (pinfunction "LC2_LC2") (pintype "bidirectional"))
    )
    (net (code "97") (name "unconnected-(B10-PadL3)") (class "Default")
      (node (ref "B10") (pin "L3") (pinfunction "L3_L3") (pintype "bidirectional"))
    )
    (net (code "98") (name "unconnected-(B10-PadL4)") (class "Default")
      (node (ref "B10") (pin "L4") (pinfunction "L4_L4") (pintype "bidirectional"))
    )
    (net (code "99") (name "unconnected-(B10-PadLC2)") (class "Default")
      (node (ref "B10") (pin "LC2") (pinfunction "LC2_LC2") (pintype "bidirectional"))
    )
    (net (code "100") (name "unconnected-(B11-PadL3)") (class "Default")
      (node (ref "B11") (pin "L3") (pinfunction "L3_L3") (pintype "bidirectional"))
    )
    (net (code "101") (name "unconnected-(B11-PadL4)") (class "Default")
      (node (ref "B11") (pin "L4") (pinfunction "L4_L4") (pintype "bidirectional"))
    )
    (net (code "102") (name "unconnected-(B11-PadLC2)") (class "Default")
      (node (ref "B11") (pin "LC2") (pinfunction "LC2_LC2") (pintype "bidirectional"))
    )
    (net (code "103") (name "unconnected-(B12-PadL3)") (class "Default")
      (node (ref "B12") (pin "L3") (pinfunction "L3_L3") (pintype "bidirectional"))
    )
    (net (code "104") (name "unconnected-(B12-PadL4)") (class "Default")
      (node (ref "B12") (pin "L4") (pinfunction "L4_L4") (pintype "bidirectional"))
    )
    (net (code "105") (name "unconnected-(B12-PadLC2)") (class "Default")
      (node (ref "B12") (pin "LC2") (pinfunction "LC2_LC2") (pintype "bidirectional"))
    )
    (net (code "106") (name "unconnected-(B13-PadL3)") (class "Default")
      (node (ref "B13") (pin "L3") (pinfunction "L3_L3") (pintype "bidirectional"))
    )
    (net (code "107") (name "unconnected-(B13-PadL4)") (class "Default")
      (node (ref "B13") (pin "L4") (pinfunction "L4_L4") (pintype "bidirectional"))
    )
    (net (code "108") (name "unconnected-(B13-PadLC2)") (class "Default")
      (node (ref "B13") (pin "LC2") (pinfunction "LC2_LC2") (pintype "bidirectional"))
    )
    (net (code "109") (name "unconnected-(B14-PadL3)") (class "Default")
      (node (ref "B14") (pin "L3") (pinfunction "L3_L3") (pintype "bidirectional"))
    )
    (net (code "110") (name "unconnected-(B14-PadL4)") (class "Default")
      (node (ref "B14") (pin "L4") (pinfunction "L4_L4") (pintype "bidirectional"))
    )
    (net (code "111") (name "unconnected-(B14-PadLC2)") (class "Default")
      (node (ref "B14") (pin "LC2") (pinfunction "LC2_LC2") (pintype "bidirectional"))
    )
    (net (code "112") (name "unconnected-(B15-PadL3)") (class "Default")
      (node (ref "B15") (pin "L3") (pinfunction "L3_L3") (pintype "bidirectional"))
    )
    (net (code "113") (name "unconnected-(B15-PadL4)") (class "Default")
      (node (ref "B15") (pin "L4") (pinfunction "L4_L4") (pintype "bidirectional"))
    )
    (net (code "114") (name "unconnected-(B15-PadLC2)") (class "Default")
      (node (ref "B15") (pin "LC2") (pinfunction "LC2_LC2") (pintype "bidirectional"))
    )
    (net (code "115") (name "unconnected-(B16-PadL3)") (class "Default")
      (node (ref "B16") (pin "L3") (pinfunction "L3_L3") (pintype "bidirectional"))
    )
    (net (code "116") (name "unconnected-(B16-PadL4)") (class "Default")
      (node (ref "B16") (pin "L4") (pinfunction "L4_L4") (pintype "bidirectional"))
    )
    (net (code "117") (name "unconnected-(B16-PadLC2)") (class "Default")
      (node (ref "B16") (pin "LC2") (pinfunction "LC2_LC2") (pintype "bidirectional"))
    )
    (net (code "118") (name "unconnected-(GND-*D5-PadD5)") (class "Default")
      (node (ref "GND") (pin "D5") (pinfunction "*D5_D5") (pintype "bidirectional"))
    )
    (net (code "119") (name "unconnected-(GND-*D6-PadD6)") (class "Default")
      (node (ref "GND") (pin "D6") (pinfunction "*D6_D6") (pintype "bidirectional"))
    )
    (net (code "120") (name "unconnected-(GND-*D9-PadD9)") (class "Default")
      (node (ref "GND") (pin "D9") (pinfunction "*D9_D9") (pintype "bidirectional"))
    )
    (net (code "121") (name "unconnected-(GND-*D10-PadD10)") (class "Default")
      (node (ref "GND") (pin "D10") (pinfunction "*D10_D10") (pintype "bidirectional"))
    )
    (net (code "122") (name "unconnected-(GND-*D11-PadD11)") (class "Default")
      (node (ref "GND") (pin "D11") (pinfunction "*D11_D11") (pintype "bidirectional"))
    )
    (net (code "123") (name "unconnected-(GND-Pad3.3V)") (class "Default")
      (node (ref "GND") (pin "3.3V") (pinfunction "3.3V_3.3V") (pintype "bidirectional"))
    )
    (net (code "124") (name "unconnected-(GND-PadA2)") (class "Default")
      (node (ref "GND") (pin "A2") (pinfunction "A2_A2") (pintype "bidirectional"))
    )
    (net (code "125") (name "unconnected-(GND-PadA3)") (class "Default")
      (node (ref "GND") (pin "A3") (pinfunction "A3_A3") (pintype "bidirectional"))
    )
    (net (code "126") (name "unconnected-(GND-PadA4)") (class "Default")
      (node (ref "GND") (pin "A4") (pinfunction "A4_A4") (pintype "bidirectional"))
    )
    (net (code "127") (name "unconnected-(GND-PadA5)") (class "Default")
      (node (ref "GND") (pin "A5") (pinfunction "A5_A5") (pintype "bidirectional"))
    )
    (net (code "128") (name "unconnected-(GND-PadAREF)") (class "Default")
      (node (ref "GND") (pin "AREF") (pinfunction "AREF_AREF") (pintype "bidirectional"))
    )
    (net (code "129") (name "unconnected-(GND-PadD4)") (class "Default")
      (node (ref "GND") (pin "D4") (pinfunction "D4_D4") (pintype "bidirectional"))
    )
    (net (code "130") (name "unconnected-(GND-PadD8)") (class "Default")
      (node (ref "GND") (pin "D8") (pinfunction "D8_D8") (pintype "bidirectional"))
    )
    (net (code "131") (name "unconnected-(GND-PadD12)") (class "Default")
      (node (ref "GND") (pin "D12") (pinfunction "D12_D12") (pintype "bidirectional"))
    )
    (net (code "132") (name "unconnected-(GND-PadD13)") (class "Default")
      (node (ref "GND") (pin "D13") (pinfunction "D13_D13") (pintype "bidirectional"))
    )
    (net (code "133") (name "unconnected-(GND-PadRX)") (class "Default")
      (node (ref "GND") (pin "RX") (pinfunction "RX_RX") (pintype "bidirectional"))
    )
    (net (code "134") (name "unconnected-(GND-PadTX)") (class "Default")
      (node (ref "GND") (pin "TX") (pinfunction "TX_TX") (pintype "bidirectional"))
    )
    (net (code "135") (name "unconnected-(IC4-INTA-Pad20)") (class "Default")
      (node (ref "IC4") (pin "20") (pinfunction "INTA_20") (pintype "output"))
    )
    (net (code "136") (name "unconnected-(IC4-INTB-Pad19)") (class "Default")
      (node (ref "IC4") (pin "19") (pinfunction "INTB_19") (pintype "output"))
    )
  )
)
